# 5.net
KiCad netlist of a schematic drawn in EasyEDA
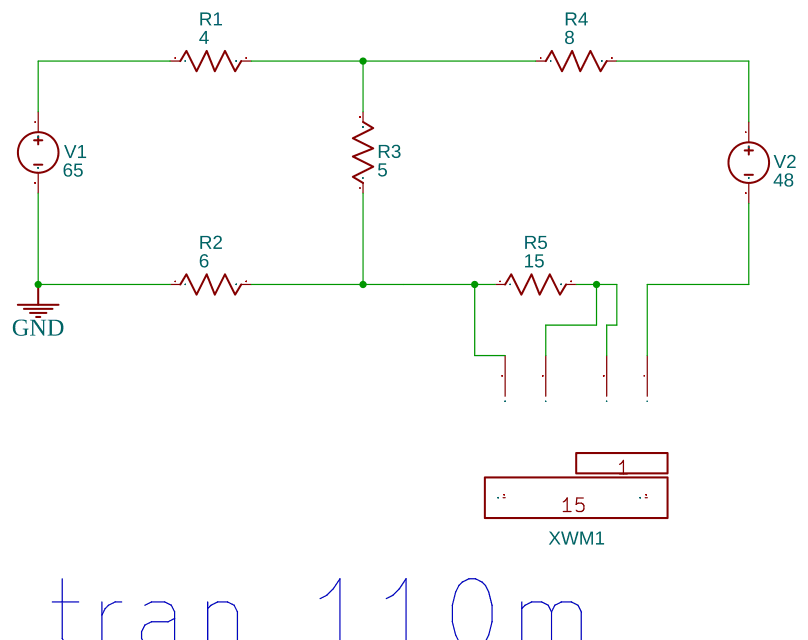
[diagram p0: schematic sheet]

(export (version "E")
  (design (tool "Eeschema 10.0.6"))
  (components
    (comp (ref "R1") (value "4") (libsource (lib "") (part "Resistor_US")))
    (comp (ref "R2") (value "6") (libsource (lib "") (part "Resistor_US")))
    (comp (ref "R3") (value "5") (libsource (lib "") (part "Resistor_US_1")))
    (comp (ref "R4") (value "8") (libsource (lib "") (part "Resistor_US")))
    (comp (ref "R5") (value "15") (libsource (lib "") (part "Resistor_US")))
    (comp (ref "V1") (value "65") (libsource (lib "") (part "VDC")))
    (comp (ref "V2") (value "48") (libsource (lib "") (part "VDC")))
    (comp (ref "XWM1") (value "Wattmeter") (libsource (lib "") (part "WATTMETER")))
  )
  (nets
    (net (code "1") (name "GND") (class "Default")
      (node (ref "R2") (pin "1") (pinfunction "1_1") (pintype "unspecified"))
      (node (ref "V1") (pin "2") (pinfunction "2_2") (pintype "unspecified"))
    )
    (net (code "2") (name "Net-(R1-Pad1)") (class "Default")
      (node (ref "R1") (pin "1") (pinfunction "1_1") (pintype "unspecified"))
      (node (ref "V1") (pin "1") (pinfunction "1_1") (pintype "unspecified"))
    )
    (net (code "3") (name "Net-(R1-Pad2)") (class "Default")
      (node (ref "R1") (pin "2") (pinfunction "2_2") (pintype "unspecified"))
      (node (ref "R3") (pin "2") (pinfunction "2_2") (pintype "unspecified"))
      (node (ref "R4") (pin "1") (pinfunction "1_1") (pintype "unspecified"))
    )
    (net (code "4") (name "Net-(R4-Pad2)") (class "Default")
      (node (ref "R4") (pin "2") (pinfunction "2_2") (pintype "unspecified"))
      (node (ref "V2") (pin "1") (pinfunction "1_1") (pintype "unspecified"))
    )
    (net (code "5") (name "Net-(XWM1-I+)") (class "Default")
      (node (ref "R5") (pin "2") (pinfunction "2_2") (pintype "unspecified"))
      (node (ref "XWM1") (pin "2") (pinfunction "V-_2") (pintype "unspecified"))
      (node (ref "XWM1") (pin "3") (pinfunction "I+_3") (pintype "unspecified"))
    )
    (net (code "6") (name "Net-(XWM1-I-)") (class "Default")
      (node (ref "V2") (pin "2") (pinfunction "2_2") (pintype "unspecified"))
      (node (ref "XWM1") (pin "4") (pinfunction "I-_4") (pintype "unspecified"))
    )
    (net (code "7") (name "Net-(XWM1-V+)") (class "Default")
      (node (ref "R2") (pin "2") (pinfunction "2_2") (pintype "unspecified"))
      (node (ref "R3") (pin "1") (pinfunction "1_1") (pintype "unspecified"))
      (node (ref "R5") (pin "1") (pinfunction "1_1") (pintype "unspecified"))
      (node (ref "XWM1") (pin "1") (pinfunction "V+_1") (pintype "unspecified"))
    )
    (net (code "8") (name "unconnected-(XWM1-PadP)") (class "Default")
      (node (ref "XWM1") (pin "P") (pinfunction "P_P") (pintype "unspecified"))
    )
    (net (code "9") (name "unconnected-(XWM1-PadPF)") (class "Default")
      (node (ref "XWM1") (pin "PF") (pinfunction "PF_PF") (pintype "unspecified"))
    )
  )
)
